# Thermometer.net
KiCad netlist of a schematic drawn in Altium Designer
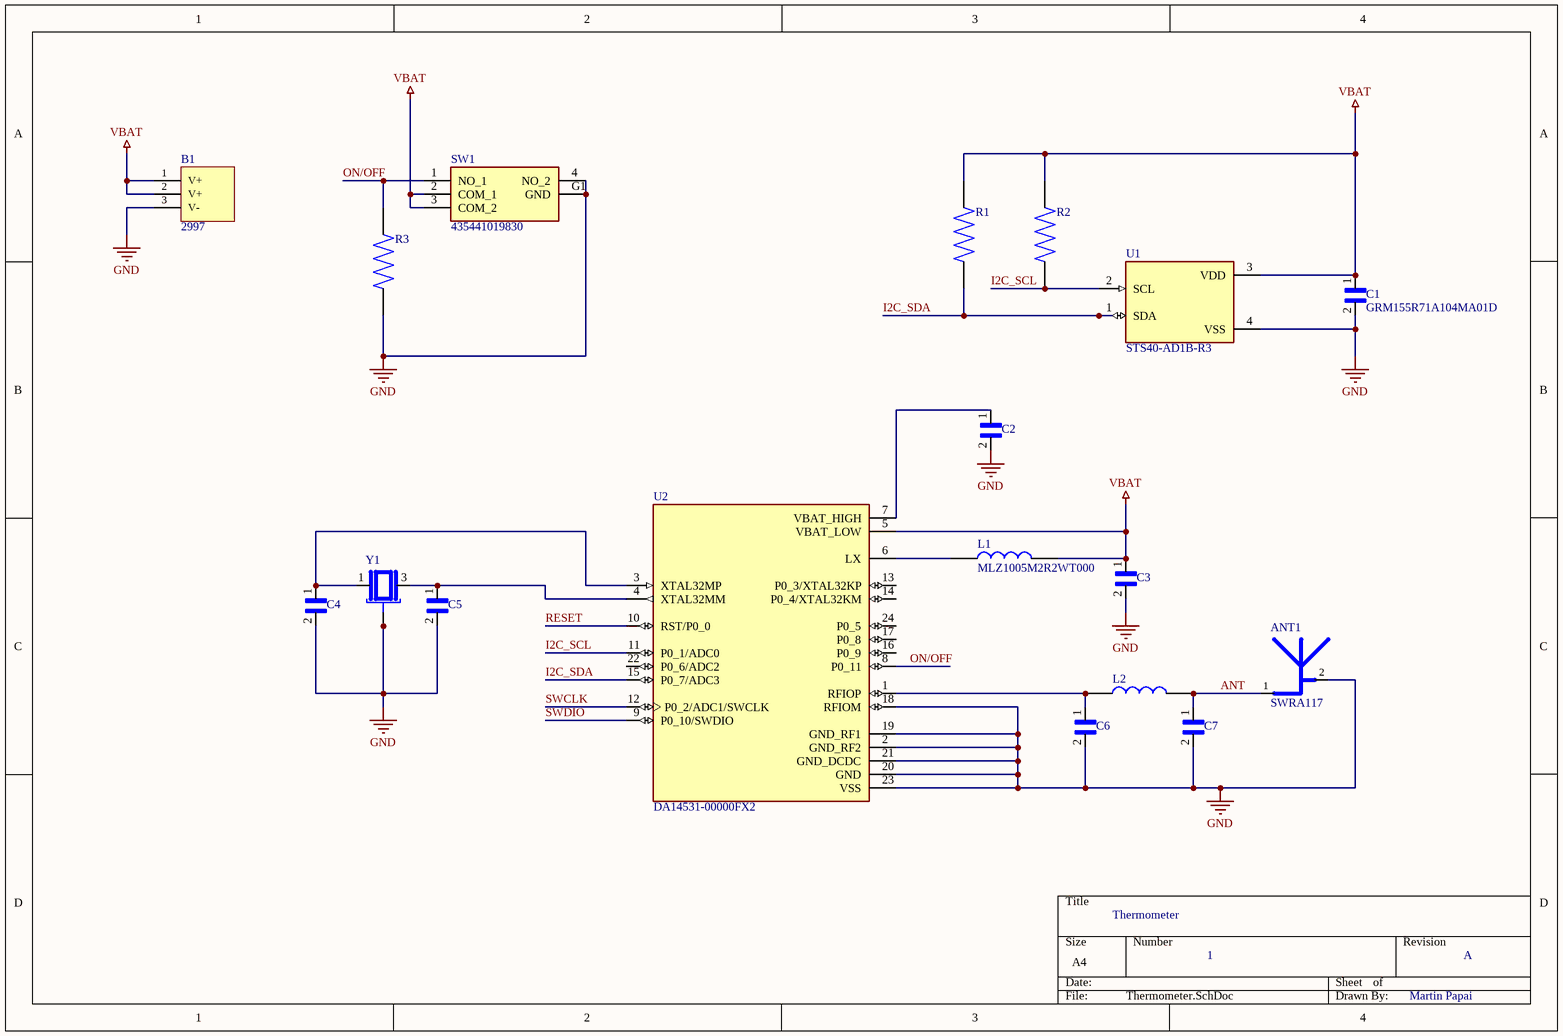
[diagram p0: Thermometer.SchDoc]

(export (version "E")
  (design (tool "Eeschema 10.0.6"))
  (components
    (comp (ref "ANT1")
      (value "SWRA117")
      (footprint "SWRA117")
      (description "TI 2.4Ghz PCB Antenna")
      (libsource (lib "SWRA117") (part "SWRA117"))
    )
    (comp (ref "B1")
      (value "2997")
      (footprint "2997")
      (description "Coin Cell Battery Holders THM .520x.585x.500 No Hole")
      (libsource (lib "2997") (part "2997"))
    )
    (comp (ref "C1")
      (value "GRM155R71A104MA01D")
      (footprint "CAPC1005X60")
      (description "Multilayer Ceramic Capacitors MLCC - SMD/SMT 0.1 uF 10 VDC 20% 0402 X7R")
      (libsource (lib "GRM155R71A104MA01D") (part "GRM155R71A104MA01D"))
    )
    (comp (ref "C2")
      (value "C0402C105K8PAC7411")
      (footprint "CAPC1005X60")
      (description "Multilayer Ceramic Capacitors MLCC - SMD/SMT 10V 1uF X5R 0402 10%")
      (libsource (lib "C0402C105K8PAC7411") (part "C0402C105K8PAC7411"))
    )
    (comp (ref "C3")
      (value "GRM155R60J106ME05J")
      (footprint "CAPC1005X60")
      (description "Multilayer Ceramic Capacitors MLCC - SMD/SMT 10 uF 6.3 VDC 20% 0402 X5R")
      (libsource (lib "GRM155R60J106ME05J") (part "GRM155R60J106ME05J"))
    )
    (comp (ref "C4")
      (value "GCM1555C1H8R0DA16D")
      (footprint "CAPC1005X60")
      (description "Multilayer Ceramic Capacitors MLCC - SMD/SMT 8 pF 50 VDC 0.5 pF 0402 C0G (NP0) AEC-Q200")
      (libsource (lib "GCM1555C1H8R0DA16D") (part "GCM1555C1H8R0DA16D"))
    )
    (comp (ref "C5")
      (value "GCM1555C1H8R0DA16D")
      (footprint "CAPC1005X60")
      (description "Multilayer Ceramic Capacitors MLCC - SMD/SMT 8 pF 50 VDC 0.5 pF 0402 C0G (NP0) AEC-Q200")
      (libsource (lib "GCM1555C1H8R0DA16D") (part "GCM1555C1H8R0DA16D"))
    )
    (comp (ref "C6")
      (value "GRM1555C2A1R8CA01D")
      (footprint "CAPC1005X60")
      (description "Multilayer Ceramic Capacitors MLCC - SMD/SMT 1.8 pF 100 VDC 0.25 pF 0402 C0G (NP0)")
      (libsource (lib "GRM1555C2A1R8CA01D") (part "GRM1555C2A1R8CA01D"))
    )
    (comp (ref "C7")
      (value "GRM1555C2A1R8CA01D")
      (footprint "CAPC1005X60")
      (description "Multilayer Ceramic Capacitors MLCC - SMD/SMT 1.8 pF 100 VDC 0.25 pF 0402 C0G (NP0)")
      (libsource (lib "GRM1555C2A1R8CA01D") (part "GRM1555C2A1R8CA01D"))
    )
    (comp (ref "L1")
      (value "MLZ1005M2R2WT000")
      (footprint "INDC1005X55N")
      (description "Inductor Power Shielded Multi-Layer 2.2uH 20% 2MHz Ferrite 350mA 715mOhm DCR 0402 T/R")
      (fields (field (name "MOUSER PART NUMBER") "810-MLZ1005M2R2WT000"))
      (libsource (lib "MLZ1005M2R2WT000") (part "MLZ1005M2R2WT000"))
    )
    (comp (ref "L2")
      (value "LQG15HN3N3S02D")
      (footprint "LQG15WH0N7B02D")
      (description "Murata LQQ15HN Series Wire-wound SMD Inductor 0.0033 uH +/-0.3nH 300mA Idc Q:8")
      (fields (field (name "MOUSER PART NUMBER") "81-LQG15HN3N3S02D"))
      (libsource (lib "LQG15HN3N3S02D") (part "LQG15HN3N3S02D"))
    )
    (comp (ref "R1")
      (value "RC0402FR-7W10KL")
      (footprint "RES1005")
      (description "Thick Film Resistors - SMD 10 kOhms 125mW 0402 1%")
      (fields (field (name "MP") "CRCW060310K0FKEBC"))
      (libsource (lib "RC0402FR-7W10KL") (part "RC0402FR-7W10KL"))
    )
    (comp (ref "R2")
      (value "RC0402FR-7W10KL")
      (footprint "RES1005")
      (description "Thick Film Resistors - SMD 10 kOhms 125mW 0402 1%")
      (fields (field (name "MP") "CRCW060310K0FKEBC"))
      (libsource (lib "RC0402FR-7W10KL") (part "RC0402FR-7W10KL"))
    )
    (comp (ref "R3")
      (value "RC0402FR-7W10KL")
      (footprint "RES1005")
      (description "Thick Film Resistors - SMD 10 kOhms 125mW 0402 1%")
      (fields (field (name "MP") "CRCW060310K0FKEBC"))
      (libsource (lib "RC0402FR-7W10KL") (part "RC0402FR-7W10KL"))
    )
    (comp (ref "SW1")
      (value "435441019830")
      (footprint "435441019830")
      (description "Tactile Switches WS-TASV Tact Switch Washable 4.1x2.8x1.9 mm SMT")
      (fields (field (name "MOUSER PART NUMBER") "710-435441019830"))
      (libsource (lib "435441019830") (part "435441019830"))
    )
    (comp (ref "U1")
      (value "STS40-AD1B-R3")
      (footprint "STS4X")
      (description "Digital Temperature Sensor, Â±0.2 Â°C, Ultra-Low-Power, I2C fast mode plus")
      (fields (field (name "MF") "Sensirion"))
      (libsource (lib "STS40-AD1B-R3") (part "STS40-AD1B-R3"))
    )
    (comp (ref "U2")
      (value "DA14531-00000FX2")
      (footprint "XCVR_DA14531-00000FX2")
      (description "IC RF TxRx + MCU Bluetooth Bluetooth v5.1 2.4GHz FCGQFN 24")
      (fields (field (name "MF") "Dialog Semiconductor GmbH"))
      (libsource (lib "DA14531-00000FX2") (part "DA14531-00000FX2"))
    )
    (comp (ref "Y1")
      (value "ECS-320-6-37B2-CKM-TR")
      (footprint "XTAL_ECS-320-6-37B2-CKM-TR")
      (fields (field (name "MF") "ECS Inc."))
      (libsource (lib "ECS-320-6-37B2-CKM-TR") (part "ECS-320-6-37B2-CKM-TR"))
    )
  )
  (nets
    (net (code "1") (name "/ANT") (class "Default")
      (node (ref "ANT1") (pin "1") (pinfunction "FP_1") (pintype "passive"))
      (node (ref "C7") (pin "1") (pinfunction "1_1") (pintype "passive"))
      (node (ref "L2") (pin "2") (pinfunction "2_2") (pintype "passive"))
    )
    (net (code "2") (name "/I2C_SCL") (class "Default")
      (node (ref "R2") (pin "1") (pinfunction "1_1") (pintype "passive"))
      (node (ref "U1") (pin "2") (pinfunction "SCL_2") (pintype "input"))
      (node (ref "U2") (pin "11") (pinfunction "P0_1/ADC0_11") (pintype "bidirectional"))
    )
    (net (code "3") (name "/I2C_SDA") (class "Default")
      (node (ref "R1") (pin "1") (pinfunction "1_1") (pintype "passive"))
      (node (ref "U1") (pin "1") (pinfunction "SDA_1") (pintype "bidirectional"))
      (node (ref "U2") (pin "15") (pinfunction "P0_7/ADC3_15") (pintype "bidirectional"))
    )
    (net (code "4") (name "/ON{slash}OFF") (class "Default")
      (node (ref "R3") (pin "2") (pinfunction "2_2") (pintype "passive"))
      (node (ref "SW1") (pin "1") (pinfunction "NO_1_1") (pintype "passive"))
      (node (ref "U2") (pin "8") (pinfunction "P0_11_8") (pintype "bidirectional"))
    )
    (net (code "5") (name "/RESET") (class "Default")
      (node (ref "U2") (pin "10") (pinfunction "RST/P0_0_10") (pintype "bidirectional"))
    )
    (net (code "6") (name "/SWCLK") (class "Default")
      (node (ref "U2") (pin "12") (pinfunction "P0_2/ADC1/SWCLK_12") (pintype "bidirectional"))
    )
    (net (code "7") (name "/SWDIO") (class "Default")
      (node (ref "U2") (pin "9") (pinfunction "P0_10/SWDIO_9") (pintype "bidirectional"))
    )
    (net (code "8") (name "GND") (class "Default")
      (node (ref "ANT1") (pin "2") (pinfunction "Ret_2") (pintype "passive"))
      (node (ref "B1") (pin "3") (pinfunction "V-_3") (pintype "passive"))
      (node (ref "C1") (pin "2") (pinfunction "2_2") (pintype "passive"))
      (node (ref "C2") (pin "2") (pinfunction "2_2") (pintype "passive"))
      (node (ref "C3") (pin "2") (pinfunction "2_2") (pintype "passive"))
      (node (ref "C4") (pin "2") (pinfunction "2_2") (pintype "passive"))
      (node (ref "C5") (pin "2") (pinfunction "2_2") (pintype "passive"))
      (node (ref "C6") (pin "2") (pinfunction "2_2") (pintype "passive"))
      (node (ref "C7") (pin "2") (pinfunction "2_2") (pintype "passive"))
      (node (ref "R3") (pin "1") (pinfunction "1_1") (pintype "passive"))
      (node (ref "SW1") (pin "4") (pinfunction "NO_2_4") (pintype "passive"))
      (node (ref "SW1") (pin "G1") (pinfunction "GND_G1") (pintype "passive"))
      (node (ref "U1") (pin "4") (pinfunction "VSS_4") (pintype "power_in"))
      (node (ref "U2") (pin "18") (pinfunction "RFIOM_18") (pintype "bidirectional"))
      (node (ref "U2") (pin "19") (pinfunction "GND_RF1_19") (pintype "power_in"))
      (node (ref "U2") (pin "2") (pinfunction "GND_RF2_2") (pintype "power_in"))
      (node (ref "U2") (pin "20") (pinfunction "GND_20") (pintype "power_in"))
      (node (ref "U2") (pin "21") (pinfunction "GND_DCDC_21") (pintype "power_in"))
      (node (ref "U2") (pin "23") (pinfunction "VSS_23") (pintype "power_in"))
      (node (ref "Y1") (pin "2") (pinfunction "GND_2") (pintype "power_in"))
      (node (ref "Y1") (pin "4") (pinfunction "GND_4") (pintype "power_in"))
    )
    (net (code "9") (name "Net-(U2-LX)") (class "Default")
      (node (ref "L1") (pin "1") (pinfunction "1_1") (pintype "passive"))
      (node (ref "U2") (pin "6") (pinfunction "LX_6") (pintype "passive"))
    )
    (net (code "10") (name "Net-(U2-RFIOP)") (class "Default")
      (node (ref "C6") (pin "1") (pinfunction "1_1") (pintype "passive"))
      (node (ref "L2") (pin "1") (pinfunction "1_1") (pintype "passive"))
      (node (ref "U2") (pin "1") (pinfunction "RFIOP_1") (pintype "bidirectional"))
    )
    (net (code "11") (name "Net-(U2-VBAT_HIGH)") (class "Default")
      (node (ref "C2") (pin "1") (pinfunction "1_1") (pintype "passive"))
      (node (ref "U2") (pin "7") (pinfunction "VBAT_HIGH_7") (pintype "power_in"))
    )
    (net (code "12") (name "Net-(U2-XTAL32MM)") (class "Default")
      (node (ref "C5") (pin "1") (pinfunction "1_1") (pintype "passive"))
      (node (ref "U2") (pin "4") (pinfunction "XTAL32MM_4") (pintype "output"))
      (node (ref "Y1") (pin "3") (pinfunction "3_3") (pintype "passive"))
    )
    (net (code "13") (name "Net-(U2-XTAL32MP)") (class "Default")
      (node (ref "C4") (pin "1") (pinfunction "1_1") (pintype "passive"))
      (node (ref "U2") (pin "3") (pinfunction "XTAL32MP_3") (pintype "input"))
      (node (ref "Y1") (pin "1") (pinfunction "1_1") (pintype "passive"))
    )
    (net (code "14") (name "VBAT") (class "Default")
      (node (ref "B1") (pin "1") (pinfunction "V+_1") (pintype "passive"))
      (node (ref "B1") (pin "2") (pinfunction "V+_2") (pintype "passive"))
      (node (ref "C1") (pin "1") (pinfunction "1_1") (pintype "passive"))
      (node (ref "C3") (pin "1") (pinfunction "1_1") (pintype "passive"))
      (node (ref "L1") (pin "2") (pinfunction "2_2") (pintype "passive"))
      (node (ref "R1") (pin "2") (pinfunction "2_2") (pintype "passive"))
      (node (ref "R2") (pin "2") (pinfunction "2_2") (pintype "passive"))
      (node (ref "SW1") (pin "2") (pinfunction "COM_1_2") (pintype "passive"))
      (node (ref "SW1") (pin "3") (pinfunction "COM_2_3") (pintype "passive"))
      (node (ref "U1") (pin "3") (pinfunction "VDD_3") (pintype "power_in"))
      (node (ref "U2") (pin "5") (pinfunction "VBAT_LOW_5") (pintype "power_in"))
    )
    (net (code "15") (name "unconnected-(U2-P0_3{slash}XTAL32KP-Pad13)") (class "Default")
      (node (ref "U2") (pin "13") (pinfunction "P0_3/XTAL32KP_13") (pintype "bidirectional"))
    )
    (net (code "16") (name "unconnected-(U2-P0_4{slash}XTAL32KM-Pad14)") (class "Default")
      (node (ref "U2") (pin "14") (pinfunction "P0_4/XTAL32KM_14") (pintype "bidirectional"))
    )
    (net (code "17") (name "unconnected-(U2-P0_5-Pad24)") (class "Default")
      (node (ref "U2") (pin "24") (pinfunction "P0_5_24") (pintype "bidirectional"))
    )
    (net (code "18") (name "unconnected-(U2-P0_6{slash}ADC2-Pad22)") (class "Default")
      (node (ref "U2") (pin "22") (pinfunction "P0_6/ADC2_22") (pintype "bidirectional"))
    )
    (net (code "19") (name "unconnected-(U2-P0_8-Pad17)") (class "Default")
      (node (ref "U2") (pin "17") (pinfunction "P0_8_17") (pintype "bidirectional"))
    )
    (net (code "20") (name "unconnected-(U2-P0_9-Pad16)") (class "Default")
      (node (ref "U2") (pin "16") (pinfunction "P0_9_16") (pintype "bidirectional"))
    )
  )
)
